# can.net
KiCad netlist of a schematic drawn in Altium Designer
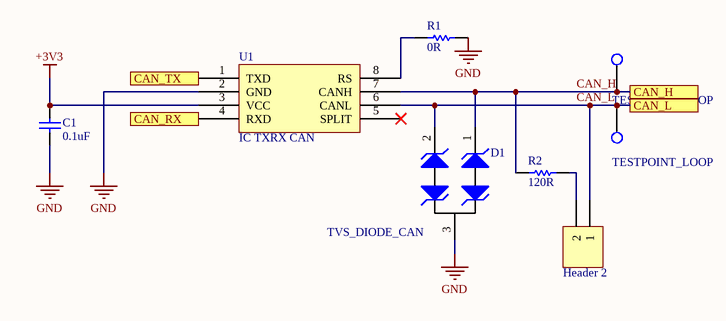
[diagram p0: can.SchDoc]

(export (version "E")
  (design (tool "Eeschema 10.0.6"))
  (components
    (comp (ref "1")
      (value "Header 2")
      (footprint "HDR1X2")
      (description "Header, 2-Pin")
      (fields (field (name "PUBLISHER") "Altium Limited"))
      (libsource (lib "Miscellaneous Connectors") (part "Header 2"))
    )
    (comp (ref "C1")
      (value "0.1uF")
      (footprint "CAPC0603(1608)55_N")
      (description "CAP CER 0.1UF 16V X7R 0603")
      (fields (field (name "PART NUMBER") "CC0603KRX7R7BB104") (field (name "MANUFACTURER") "Yageo"))
      (libsource (lib "UWRT_Schematic_Library_2019") (part "CAP_0.1uF_16V_0603"))
    )
    (comp (ref "CANH1")
      (value "TESTPOINT_LOOP")
      (footprint "TESTPOINT_LOOP")
      (libsource (lib "UWRT_Schematic_Library_2019") (part "TESTPOINT_LOOP"))
    )
    (comp (ref "CANL1")
      (value "TESTPOINT_LOOP")
      (footprint "TESTPOINT_LOOP")
      (libsource (lib "UWRT_Schematic_Library_2019") (part "TESTPOINT_LOOP"))
    )
    (comp (ref "D1")
      (value "TVS_DIODE_CAN")
      (footprint "UWRT_Footprint_Library_2019:TVS_DIODE_CAN")
      (description "TVS DIODE 24V 41V SOT323-3")
      (fields (field (name "PART NUMBER") "PESD2CAN,215") (field (name "MANUFACTURER") "Nexperia USA Inc."))
      (libsource (lib "UWRT_Schematic_Library_2019") (part "TVS_DIODE_CAN"))
    )
    (comp (ref "R1")
      (value "0R")
      (footprint "RESC0603(1608)_N")
      (description "RES SMD 0 OHM JUMPER 1/10W 0603")
      (fields (field (name "MANUFACTURER") "Yageo") (field (name "Comment") "RES_0R_0603"))
      (libsource (lib "UWRT_Schematic_Library_2019") (part "RES_0R_0603"))
    )
    (comp (ref "R2")
      (value "120R")
      (footprint "RESC0603(1608)_N")
      (description "RES SMD 120 OHM 5% 1/10W 0603")
      (fields (field (name "MANUFACTURER") "Yageo") (field (name "TOLERANCE") "5%"))
      (libsource (lib "UWRT_Schematic_Library_2019") (part "RES_120R_0603"))
    )
    (comp (ref "U1")
      (value "IC TXRX CAN")
      (footprint "LTC2875")
      (description "IC TXRX CAN 4MBPS 8SO")
      (fields
        (field (name "MANUFACTURER") "Linear Technologies")
        (field (name "PART NUMBER") "LTC2875IS8#PBF")
      )
      (libsource (lib "UWRT_Schematic_Library_2019") (part "LTC2875"))
    )
  )
  (nets
    (net (code "1") (name "+3V3") (class "Default")
      (node (ref "C1") (pin "2") (pinfunction "2_2") (pintype "passive"))
      (node (ref "U1") (pin "3") (pinfunction "VCC_3") (pintype "passive"))
    )
    (net (code "2") (name "/CAN_H") (class "Default")
      (node (ref "CANH1") (pin "1") (pinfunction "=value_1") (pintype "passive"))
      (node (ref "D1") (pin "1") (pinfunction "1_1") (pintype "passive"))
      (node (ref "R2") (pin "1") (pinfunction "1_1") (pintype "passive"))
      (node (ref "U1") (pin "7") (pinfunction "CANH_7") (pintype "passive"))
    )
    (net (code "3") (name "/CAN_L") (class "Default")
      (node (ref "1") (pin "1") (pinfunction "1_1") (pintype "passive"))
      (node (ref "CANL1") (pin "1") (pinfunction "=value_1") (pintype "passive"))
      (node (ref "D1") (pin "2") (pinfunction "2_2") (pintype "passive"))
      (node (ref "U1") (pin "6") (pinfunction "CANL_6") (pintype "passive"))
    )
    (net (code "4") (name "/CAN_RX") (class "Default")
      (node (ref "U1") (pin "4") (pinfunction "RXD_4") (pintype "passive"))
    )
    (net (code "5") (name "/CAN_TX") (class "Default")
      (node (ref "U1") (pin "1") (pinfunction "TXD_1") (pintype "passive"))
    )
    (net (code "6") (name "GND") (class "Default")
      (node (ref "C1") (pin "1") (pinfunction "1_1") (pintype "passive"))
      (node (ref "D1") (pin "3") (pinfunction "3_3") (pintype "passive"))
      (node (ref "R1") (pin "2") (pinfunction "2_2") (pintype "passive"))
      (node (ref "U1") (pin "2") (pinfunction "GND_2") (pintype "passive"))
    )
    (net (code "7") (name "Net-(1-Pad2)") (class "Default")
      (node (ref "1") (pin "2") (pinfunction "2_2") (pintype "passive"))
      (node (ref "R2") (pin "2") (pinfunction "2_2") (pintype "passive"))
    )
    (net (code "8") (name "Net-(U1-RS)") (class "Default")
      (node (ref "R1") (pin "1") (pinfunction "1_1") (pintype "passive"))
      (node (ref "U1") (pin "8") (pinfunction "RS_8") (pintype "passive"))
    )
    (net (code "9") (name "unconnected-(U1-SPLIT-Pad5)") (class "Default")
      (node (ref "U1") (pin "5") (pinfunction "SPLIT_5") (pintype "passive+no_connect"))
    )
  )
)
